# ir-control.net
KiCad netlist of a schematic drawn in EAGLE
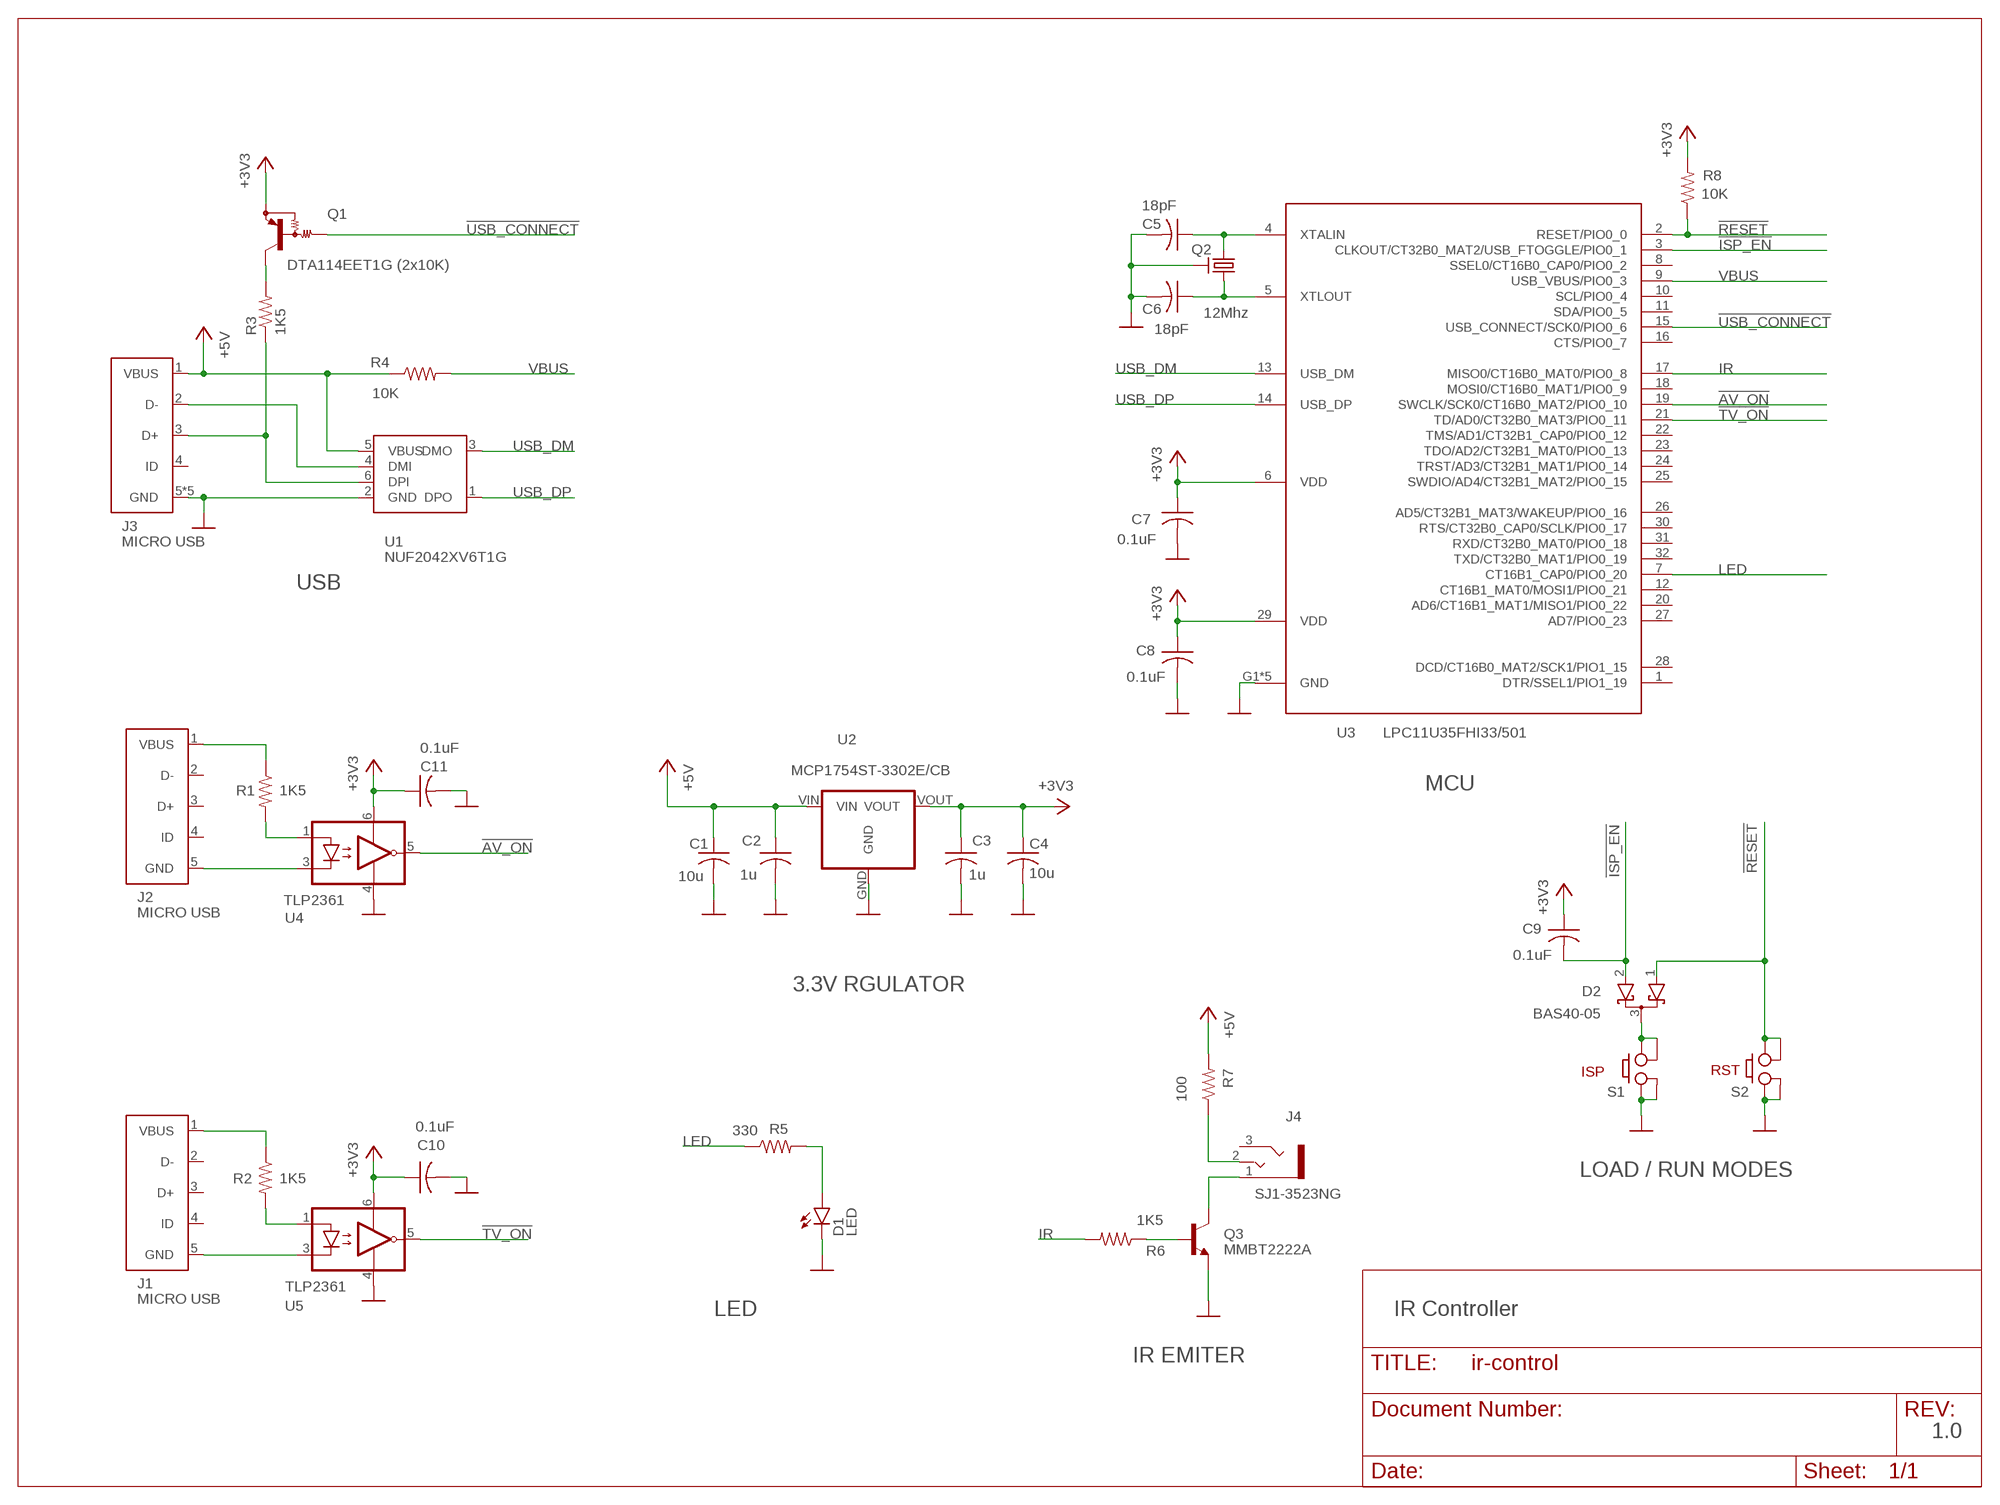
[diagram p0: schematic, sheet 1]

(export (version "E")
  (design (tool "Eeschema 10.0.6"))
  (components
    (comp (ref "C1")
      (value "10u")
      (footprint "eagle-import:C0805K")
      (libsource (lib "eagle-import") (part "CC0805K"))
    )
    (comp (ref "C2")
      (value "1u")
      (footprint "eagle-import:C0603K")
      (libsource (lib "eagle-import") (part "CC0603K"))
    )
    (comp (ref "C3")
      (value "1u")
      (footprint "eagle-import:C0603K")
      (libsource (lib "eagle-import") (part "CC0603K"))
    )
    (comp (ref "C4")
      (value "10u")
      (footprint "eagle-import:C0805K")
      (libsource (lib "eagle-import") (part "CC0805K"))
    )
    (comp (ref "C5")
      (value "18pF")
      (footprint "eagle-import:C0402K")
      (libsource (lib "eagle-import") (part "CC0402K"))
    )
    (comp (ref "C6")
      (value "18pF")
      (footprint "eagle-import:C0402K")
      (libsource (lib "eagle-import") (part "CC0402K"))
    )
    (comp (ref "C7")
      (value "0.1uF")
      (footprint "eagle-import:C0402K")
      (libsource (lib "eagle-import") (part "CC0402K"))
    )
    (comp (ref "C8")
      (value "0.1uF")
      (footprint "eagle-import:C0402K")
      (libsource (lib "eagle-import") (part "CC0402K"))
    )
    (comp (ref "C9")
      (value "0.1uF")
      (footprint "eagle-import:C0402K")
      (libsource (lib "eagle-import") (part "CC0402K"))
    )
    (comp (ref "C10")
      (value "0.1uF")
      (footprint "eagle-import:C0402K")
      (libsource (lib "eagle-import") (part "CC0402K"))
    )
    (comp (ref "C11")
      (value "0.1uF")
      (footprint "eagle-import:C0402K")
      (libsource (lib "eagle-import") (part "CC0402K"))
    )
    (comp (ref "D1")
      (value "LED")
      (footprint "eagle-import:LED")
      (libsource (lib "eagle-import") (part "LED"))
    )
    (comp (ref "D2")
      (value "BAS40-05")
      (footprint "eagle-import:SOT23")
      (libsource (lib "eagle-import") (part "BAS40-05"))
    )
    (comp (ref "J1")
      (value "MICRO USB")
      (footprint "eagle-import:USB-MICRO")
      (libsource (lib "eagle-import") (part "USB-CONN-UNSHIELDED"))
    )
    (comp (ref "J2")
      (value "MICRO USB")
      (footprint "eagle-import:USB-MICRO")
      (libsource (lib "eagle-import") (part "USB-CONN-UNSHIELDED"))
    )
    (comp (ref "J3")
      (value "MICRO USB")
      (footprint "eagle-import:USB-MICRO")
      (libsource (lib "eagle-import") (part "USB-CONN"))
    )
    (comp (ref "J4")
      (value "SJ1-3523NG")
      (footprint "eagle-import:JACK")
      (fields (field (name "MPN") "KLBR 1"))
      (libsource (lib "eagle-import") (part "JACKX"))
    )
    (comp (ref "Q1")
      (value "DTA114EET1G (2x10K)")
      (footprint "eagle-import:SC75-BEC")
      (libsource (lib "eagle-import") (part "PNP-BIASED"))
    )
    (comp (ref "Q2")
      (value "12Mhz")
      (footprint "eagle-import:CRYSTAL")
      (libsource (lib "eagle-import") (part "CRYSTALCTS406"))
    )
    (comp (ref "Q3")
      (value "MMBT2222A")
      (footprint "eagle-import:SOT23")
      (libsource (lib "eagle-import") (part "NPN"))
    )
    (comp (ref "R1")
      (value "1K5")
      (footprint "eagle-import:R0402")
      (libsource (lib "eagle-import") (part "RR0402"))
    )
    (comp (ref "R2")
      (value "1K5")
      (footprint "eagle-import:R0402")
      (libsource (lib "eagle-import") (part "RR0402"))
    )
    (comp (ref "R3")
      (value "1K5")
      (footprint "eagle-import:R0402")
      (libsource (lib "eagle-import") (part "RR0402"))
    )
    (comp (ref "R4")
      (value "10K")
      (footprint "eagle-import:R0402")
      (libsource (lib "eagle-import") (part "RR0402"))
    )
    (comp (ref "R5")
      (value "330")
      (footprint "eagle-import:R0402")
      (libsource (lib "eagle-import") (part "RR0402"))
    )
    (comp (ref "R6")
      (value "1K5")
      (footprint "eagle-import:R0402")
      (libsource (lib "eagle-import") (part "RR0402"))
    )
    (comp (ref "R7")
      (value "100")
      (footprint "eagle-import:R0402")
      (libsource (lib "eagle-import") (part "RR0402"))
    )
    (comp (ref "R8")
      (value "10K")
      (footprint "eagle-import:R0402")
      (libsource (lib "eagle-import") (part "RR0402"))
    )
    (comp (ref "S1")
      (value "CKN10502CT-ND")
      (footprint "eagle-import:PUSH_BUTTON")
      (libsource (lib "eagle-import") (part "PUSH-BUTTON"))
    )
    (comp (ref "S2")
      (value "PUSH-BUTTON")
      (footprint "eagle-import:PUSH_BUTTON")
      (libsource (lib "eagle-import") (part "PUSH-BUTTON"))
    )
    (comp (ref "U1")
      (value "NUF2042XV6T1G")
      (footprint "eagle-import:SOT-563")
      (libsource (lib "eagle-import") (part "USB-ESD"))
    )
    (comp (ref "U2")
      (value "MCP1754ST-3302E/CB")
      (footprint "eagle-import:SOT-23A")
      (libsource (lib "eagle-import") (part "LDO"))
    )
    (comp (ref "U3")
      (value "LPC11U35FHI33/501")
      (footprint "eagle-import:HVQFN33-5MM")
      (libsource (lib "eagle-import") (part "LPC11U35FHN33/501"))
    )
    (comp (ref "U4")
      (value "TLP2361")
      (footprint "eagle-import:SO6")
      (libsource (lib "eagle-import") (part "OPTO_COUPLER"))
    )
    (comp (ref "U5")
      (value "TLP2361")
      (footprint "eagle-import:SO6")
      (libsource (lib "eagle-import") (part "OPTO_COUPLER"))
    )
  )
  (nets
    (net (code "1") (name "+3V3") (class "Default")
      (node (ref "C10") (pin "1") (pinfunction "1_1") (pintype "passive"))
      (node (ref "C11") (pin "1") (pinfunction "1_1") (pintype "passive"))
      (node (ref "C3") (pin "1") (pinfunction "1_1") (pintype "passive"))
      (node (ref "C4") (pin "1") (pinfunction "1_1") (pintype "passive"))
      (node (ref "C7") (pin "1") (pinfunction "1_1") (pintype "passive"))
      (node (ref "C8") (pin "1") (pinfunction "1_1") (pintype "passive"))
      (node (ref "C9") (pin "1") (pinfunction "1_1") (pintype "passive"))
      (node (ref "Q1") (pin "E") (pinfunction "E_E") (pintype "passive"))
      (node (ref "R8") (pin "2") (pinfunction "2_2") (pintype "passive"))
      (node (ref "U2") (pin "VOUT") (pinfunction "VOUT_VOUT") (pintype "power_in"))
      (node (ref "U3") (pin "29") (pinfunction "VDD_29") (pintype "bidirectional"))
      (node (ref "U3") (pin "6") (pinfunction "VDD_6") (pintype "bidirectional"))
      (node (ref "U4") (pin "6") (pinfunction "VCC_6") (pintype "passive"))
      (node (ref "U5") (pin "6") (pinfunction "VCC_6") (pintype "passive"))
    )
    (net (code "2") (name "+5V") (class "Default")
      (node (ref "C1") (pin "1") (pinfunction "1_1") (pintype "passive"))
      (node (ref "C2") (pin "1") (pinfunction "1_1") (pintype "passive"))
      (node (ref "J3") (pin "1") (pinfunction "VBUS_1") (pintype "bidirectional"))
      (node (ref "R4") (pin "1") (pinfunction "1_1") (pintype "passive"))
      (node (ref "R7") (pin "2") (pinfunction "2_2") (pintype "passive"))
      (node (ref "U1") (pin "5") (pinfunction "VBUS_5") (pintype "power_in"))
      (node (ref "U2") (pin "VIN") (pinfunction "VIN_VIN") (pintype "power_in"))
    )
    (net (code "3") (name "/IR") (class "Default")
      (node (ref "R6") (pin "2") (pinfunction "2_2") (pintype "passive"))
      (node (ref "U3") (pin "17") (pinfunction "MISO0/CT16B0_MAT0/PIO0_8_17") (pintype "bidirectional"))
    )
    (net (code "4") (name "/LED") (class "Default")
      (node (ref "R5") (pin "1") (pinfunction "1_1") (pintype "passive"))
      (node (ref "U3") (pin "7") (pinfunction "CT16B1_CAP0/PIO0_20_7") (pintype "bidirectional"))
    )
    (net (code "5") (name "/USB_DM") (class "Default")
      (node (ref "U1") (pin "3") (pinfunction "DMO_3") (pintype "passive"))
      (node (ref "U3") (pin "13") (pinfunction "USB_DM_13") (pintype "bidirectional"))
    )
    (net (code "6") (name "/USB_DP") (class "Default")
      (node (ref "U1") (pin "1") (pinfunction "DPO_1") (pintype "passive"))
      (node (ref "U3") (pin "14") (pinfunction "USB_DP_14") (pintype "bidirectional"))
    )
    (net (code "7") (name "/VBUS") (class "Default")
      (node (ref "R4") (pin "2") (pinfunction "2_2") (pintype "passive"))
      (node (ref "U3") (pin "9") (pinfunction "USB_VBUS/PIO0_3_9") (pintype "bidirectional"))
    )
    (net (code "8") (name "/~{AV_ON}") (class "Default")
      (node (ref "U3") (pin "19") (pinfunction "SWCLK/SCK0/CT16B0_MAT2/PIO0_10_19") (pintype "bidirectional"))
      (node (ref "U4") (pin "5") (pinfunction "OUT_5") (pintype "passive"))
    )
    (net (code "9") (name "/~{ISP_EN}") (class "Default")
      (node (ref "C9") (pin "2") (pinfunction "2_2") (pintype "passive"))
      (node (ref "D2") (pin "2") (pinfunction "A2_2") (pintype "passive"))
      (node (ref "U3") (pin "3") (pinfunction "CLKOUT/CT32B0_MAT2/USB_FTOGGLE/PIO0_1_3") (pintype "bidirectional"))
    )
    (net (code "10") (name "/~{RESET}") (class "Default")
      (node (ref "D2") (pin "1") (pinfunction "A1_1") (pintype "passive"))
      (node (ref "R8") (pin "1") (pinfunction "1_1") (pintype "passive"))
      (node (ref "S2") (pin "B1") (pinfunction "B1_B1") (pintype "passive"))
      (node (ref "S2") (pin "B1P") (pinfunction "B1_B1P") (pintype "passive"))
      (node (ref "S2") (pin "B2") (pinfunction "B2_B2") (pintype "passive"))
      (node (ref "S2") (pin "B2P") (pinfunction "B2_B2P") (pintype "passive"))
      (node (ref "U3") (pin "2") (pinfunction "RESET/PIO0_0_2") (pintype "bidirectional"))
    )
    (net (code "11") (name "/~{TV_ON}") (class "Default")
      (node (ref "U3") (pin "21") (pinfunction "TD/AD0/CT32B0_MAT3/PIO0_11_21") (pintype "bidirectional"))
      (node (ref "U5") (pin "5") (pinfunction "OUT_5") (pintype "passive"))
    )
    (net (code "12") (name "/~{USB_CONNECT}") (class "Default")
      (node (ref "Q1") (pin "B") (pinfunction "B_B") (pintype "passive"))
      (node (ref "U3") (pin "15") (pinfunction "USB_CONNECT/SCK0/PIO0_6_15") (pintype "bidirectional"))
    )
    (net (code "13") (name "GND") (class "Default")
      (node (ref "C1") (pin "2") (pinfunction "2_2") (pintype "passive"))
      (node (ref "C10") (pin "2") (pinfunction "2_2") (pintype "passive"))
      (node (ref "C11") (pin "2") (pinfunction "2_2") (pintype "passive"))
      (node (ref "C2") (pin "2") (pinfunction "2_2") (pintype "passive"))
      (node (ref "C3") (pin "2") (pinfunction "2_2") (pintype "passive"))
      (node (ref "C4") (pin "2") (pinfunction "2_2") (pintype "passive"))
      (node (ref "C5") (pin "2") (pinfunction "2_2") (pintype "passive"))
      (node (ref "C6") (pin "2") (pinfunction "2_2") (pintype "passive"))
      (node (ref "C7") (pin "2") (pinfunction "2_2") (pintype "passive"))
      (node (ref "C8") (pin "2") (pinfunction "2_2") (pintype "passive"))
      (node (ref "D1") (pin "K") (pinfunction "C_K") (pintype "passive"))
      (node (ref "J3") (pin "5") (pinfunction "GND_5") (pintype "bidirectional"))
      (node (ref "J3") (pin "G1") (pinfunction "GND_G1") (pintype "bidirectional"))
      (node (ref "J3") (pin "G2") (pinfunction "GND_G2") (pintype "bidirectional"))
      (node (ref "J3") (pin "G3") (pinfunction "GND_G3") (pintype "bidirectional"))
      (node (ref "J3") (pin "G4") (pinfunction "GND_G4") (pintype "bidirectional"))
      (node (ref "Q2") (pin "2") (pinfunction "GND_2") (pintype "power_in"))
      (node (ref "Q2") (pin "4") (pinfunction "GND_4") (pintype "power_in"))
      (node (ref "Q3") (pin "2") (pinfunction "E_2") (pintype "passive"))
      (node (ref "S1") (pin "A1") (pinfunction "A1_A1") (pintype "passive"))
      (node (ref "S1") (pin "A1P") (pinfunction "A1_A1P") (pintype "passive"))
      (node (ref "S1") (pin "A2") (pinfunction "A2_A2") (pintype "passive"))
      (node (ref "S1") (pin "A2P") (pinfunction "A2_A2P") (pintype "passive"))
      (node (ref "S2") (pin "A1") (pinfunction "A1_A1") (pintype "passive"))
      (node (ref "S2") (pin "A1P") (pinfunction "A1_A1P") (pintype "passive"))
      (node (ref "S2") (pin "A2") (pinfunction "A2_A2") (pintype "passive"))
      (node (ref "S2") (pin "A2P") (pinfunction "A2_A2P") (pintype "passive"))
      (node (ref "U1") (pin "2") (pinfunction "GND_2") (pintype "power_in"))
      (node (ref "U2") (pin "GND") (pinfunction "GND_GND") (pintype "power_in"))
      (node (ref "U3") (pin "G1") (pinfunction "GND_G1") (pintype "bidirectional"))
      (node (ref "U3") (pin "G2") (pinfunction "GND_G2") (pintype "bidirectional"))
      (node (ref "U3") (pin "G3") (pinfunction "GND_G3") (pintype "bidirectional"))
      (node (ref "U3") (pin "G4") (pinfunction "GND_G4") (pintype "bidirectional"))
      (node (ref "U3") (pin "TAB") (pinfunction "GND_TAB") (pintype "bidirectional"))
      (node (ref "U4") (pin "4") (pinfunction "GND_4") (pintype "passive"))
      (node (ref "U5") (pin "4") (pinfunction "GND_4") (pintype "passive"))
    )
    (net (code "14") (name "Net-(D1-PadA)") (class "Default")
      (node (ref "D1") (pin "A") (pinfunction "A_A") (pintype "passive"))
      (node (ref "R5") (pin "2") (pinfunction "2_2") (pintype "passive"))
    )
    (net (code "15") (name "Net-(D2-C)") (class "Default")
      (node (ref "D2") (pin "3") (pinfunction "C_3") (pintype "passive"))
      (node (ref "S1") (pin "B1") (pinfunction "B1_B1") (pintype "passive"))
      (node (ref "S1") (pin "B1P") (pinfunction "B1_B1P") (pintype "passive"))
      (node (ref "S1") (pin "B2") (pinfunction "B2_B2") (pintype "passive"))
      (node (ref "S1") (pin "B2P") (pinfunction "B2_B2P") (pintype "passive"))
    )
    (net (code "16") (name "Net-(J1-GND)") (class "Default")
      (node (ref "J1") (pin "5") (pinfunction "GND_5") (pintype "bidirectional"))
      (node (ref "U5") (pin "3") (pinfunction "C_3") (pintype "passive"))
    )
    (net (code "17") (name "Net-(J1-VBUS)") (class "Default")
      (node (ref "J1") (pin "1") (pinfunction "VBUS_1") (pintype "bidirectional"))
      (node (ref "R2") (pin "1") (pinfunction "1_1") (pintype "passive"))
    )
    (net (code "18") (name "Net-(J2-GND)") (class "Default")
      (node (ref "J2") (pin "5") (pinfunction "GND_5") (pintype "bidirectional"))
      (node (ref "U4") (pin "3") (pinfunction "C_3") (pintype "passive"))
    )
    (net (code "19") (name "Net-(J2-VBUS)") (class "Default")
      (node (ref "J2") (pin "1") (pinfunction "VBUS_1") (pintype "bidirectional"))
      (node (ref "R1") (pin "1") (pinfunction "1_1") (pintype "passive"))
    )
    (net (code "20") (name "Net-(J3-D+)") (class "Default")
      (node (ref "J3") (pin "3") (pinfunction "D+_3") (pintype "bidirectional"))
      (node (ref "R3") (pin "1") (pinfunction "1_1") (pintype "passive"))
      (node (ref "U1") (pin "6") (pinfunction "DPI_6") (pintype "passive"))
    )
    (net (code "21") (name "Net-(J3-D-)") (class "Default")
      (node (ref "J3") (pin "2") (pinfunction "D-_2") (pintype "bidirectional"))
      (node (ref "U1") (pin "4") (pinfunction "DMI_4") (pintype "passive"))
    )
    (net (code "22") (name "Net-(J4-Pad2)") (class "Default")
      (node (ref "J4") (pin "2") (pinfunction "2_2") (pintype "passive"))
      (node (ref "R7") (pin "1") (pinfunction "1_1") (pintype "passive"))
    )
    (net (code "23") (name "Net-(Q1-PadC)") (class "Default")
      (node (ref "Q1") (pin "C") (pinfunction "C_C") (pintype "passive"))
      (node (ref "R3") (pin "2") (pinfunction "2_2") (pintype "passive"))
    )
    (net (code "24") (name "Net-(Q2-2)") (class "Default")
      (node (ref "C5") (pin "1") (pinfunction "1_1") (pintype "passive"))
      (node (ref "Q2") (pin "3") (pinfunction "2_3") (pintype "passive"))
      (node (ref "U3") (pin "4") (pinfunction "XTALIN_4") (pintype "bidirectional"))
    )
    (net (code "25") (name "Net-(Q3-B)") (class "Default")
      (node (ref "Q3") (pin "1") (pinfunction "B_1") (pintype "passive"))
      (node (ref "R6") (pin "1") (pinfunction "1_1") (pintype "passive"))
    )
    (net (code "26") (name "Net-(Q3-C)") (class "Default")
      (node (ref "J4") (pin "1") (pinfunction "1_1") (pintype "passive"))
      (node (ref "Q3") (pin "3") (pinfunction "C_3") (pintype "passive"))
    )
    (net (code "27") (name "Net-(U3-XTLOUT)") (class "Default")
      (node (ref "C6") (pin "1") (pinfunction "1_1") (pintype "passive"))
      (node (ref "Q2") (pin "1") (pinfunction "1_1") (pintype "passive"))
      (node (ref "U3") (pin "5") (pinfunction "XTLOUT_5") (pintype "bidirectional"))
    )
    (net (code "28") (name "Net-(U4-A)") (class "Default")
      (node (ref "R1") (pin "2") (pinfunction "2_2") (pintype "passive"))
      (node (ref "U4") (pin "1") (pinfunction "A_1") (pintype "passive"))
    )
    (net (code "29") (name "Net-(U5-A)") (class "Default")
      (node (ref "R2") (pin "2") (pinfunction "2_2") (pintype "passive"))
      (node (ref "U5") (pin "1") (pinfunction "A_1") (pintype "passive"))
    )
    (net (code "30") (name "unconnected-(J1-D+-Pad3)") (class "Default")
      (node (ref "J1") (pin "3") (pinfunction "D+_3") (pintype "bidirectional"))
    )
    (net (code "31") (name "unconnected-(J1-D--Pad2)") (class "Default")
      (node (ref "J1") (pin "2") (pinfunction "D-_2") (pintype "bidirectional"))
    )
    (net (code "32") (name "unconnected-(J1-ID-Pad4)") (class "Default")
      (node (ref "J1") (pin "4") (pinfunction "ID_4") (pintype "bidirectional"))
    )
    (net (code "33") (name "unconnected-(J2-D+-Pad3)") (class "Default")
      (node (ref "J2") (pin "3") (pinfunction "D+_3") (pintype "bidirectional"))
    )
    (net (code "34") (name "unconnected-(J2-D--Pad2)") (class "Default")
      (node (ref "J2") (pin "2") (pinfunction "D-_2") (pintype "bidirectional"))
    )
    (net (code "35") (name "unconnected-(J2-ID-Pad4)") (class "Default")
      (node (ref "J2") (pin "4") (pinfunction "ID_4") (pintype "bidirectional"))
    )
    (net (code "36") (name "unconnected-(J3-ID-Pad4)") (class "Default")
      (node (ref "J3") (pin "4") (pinfunction "ID_4") (pintype "bidirectional"))
    )
    (net (code "37") (name "unconnected-(J4-Pad3)") (class "Default")
      (node (ref "J4") (pin "3") (pinfunction "3_3") (pintype "passive"))
    )
    (net (code "38") (name "unconnected-(U3-AD5{slash}CT32B1_MAT3{slash}WAKEUP{slash}PIO0_16-Pad26)") (class "Default")
      (node (ref "U3") (pin "26") (pinfunction "AD5/CT32B1_MAT3/WAKEUP/PIO0_16_26") (pintype "bidirectional"))
    )
    (net (code "39") (name "unconnected-(U3-AD6{slash}CT16B1_MAT1{slash}MISO1{slash}PIO0_22-Pad20)") (class "Default")
      (node (ref "U3") (pin "20") (pinfunction "AD6/CT16B1_MAT1/MISO1/PIO0_22_20") (pintype "bidirectional"))
    )
    (net (code "40") (name "unconnected-(U3-AD7{slash}PIO0_23-Pad27)") (class "Default")
      (node (ref "U3") (pin "27") (pinfunction "AD7/PIO0_23_27") (pintype "bidirectional"))
    )
    (net (code "41") (name "unconnected-(U3-CT16B1_MAT0{slash}MOSI1{slash}PIO0_21-Pad12)") (class "Default")
      (node (ref "U3") (pin "12") (pinfunction "CT16B1_MAT0/MOSI1/PIO0_21_12") (pintype "bidirectional"))
    )
    (net (code "42") (name "unconnected-(U3-CTS{slash}PIO0_7-Pad16)") (class "Default")
      (node (ref "U3") (pin "16") (pinfunction "CTS/PIO0_7_16") (pintype "bidirectional"))
    )
    (net (code "43") (name "unconnected-(U3-DCD{slash}CT16B0_MAT2{slash}SCK1{slash}PIO1_15-Pad28)") (class "Default")
      (node (ref "U3") (pin "28") (pinfunction "DCD/CT16B0_MAT2/SCK1/PIO1_15_28") (pintype "bidirectional"))
    )
    (net (code "44") (name "unconnected-(U3-DTR{slash}SSEL1{slash}PIO1_19-Pad1)") (class "Default")
      (node (ref "U3") (pin "1") (pinfunction "DTR/SSEL1/PIO1_19_1") (pintype "bidirectional"))
    )
    (net (code "45") (name "unconnected-(U3-MOSI0{slash}CT16B0_MAT1{slash}PIO0_9-Pad18)") (class "Default")
      (node (ref "U3") (pin "18") (pinfunction "MOSI0/CT16B0_MAT1/PIO0_9_18") (pintype "bidirectional"))
    )
    (net (code "46") (name "unconnected-(U3-RTS{slash}CT32B0_CAP0{slash}SCLK{slash}PIO0_17-Pad30)") (class "Default")
      (node (ref "U3") (pin "30") (pinfunction "RTS/CT32B0_CAP0/SCLK/PIO0_17_30") (pintype "bidirectional"))
    )
    (net (code "47") (name "unconnected-(U3-RXD{slash}CT32B0_MAT0{slash}PIO0_18-Pad31)") (class "Default")
      (node (ref "U3") (pin "31") (pinfunction "RXD/CT32B0_MAT0/PIO0_18_31") (pintype "bidirectional"))
    )
    (net (code "48") (name "unconnected-(U3-SCL{slash}PIO0_4-Pad10)") (class "Default")
      (node (ref "U3") (pin "10") (pinfunction "SCL/PIO0_4_10") (pintype "bidirectional"))
    )
    (net (code "49") (name "unconnected-(U3-SDA{slash}PIO0_5-Pad11)") (class "Default")
      (node (ref "U3") (pin "11") (pinfunction "SDA/PIO0_5_11") (pintype "bidirectional"))
    )
    (net (code "50") (name "unconnected-(U3-SSEL0{slash}CT16B0_CAP0{slash}PIO0_2-Pad8)") (class "Default")
      (node (ref "U3") (pin "8") (pinfunction "SSEL0/CT16B0_CAP0/PIO0_2_8") (pintype "bidirectional"))
    )
    (net (code "51") (name "unconnected-(U3-SWDIO{slash}AD4{slash}CT32B1_MAT2{slash}PIO0_15-Pad25)") (class "Default")
      (node (ref "U3") (pin "25") (pinfunction "SWDIO/AD4/CT32B1_MAT2/PIO0_15_25") (pintype "bidirectional"))
    )
    (net (code "52") (name "unconnected-(U3-TDO{slash}AD2{slash}CT32B1_MAT0{slash}PIO0_13-Pad23)") (class "Default")
      (node (ref "U3") (pin "23") (pinfunction "TDO/AD2/CT32B1_MAT0/PIO0_13_23") (pintype "bidirectional"))
    )
    (net (code "53") (name "unconnected-(U3-TMS{slash}AD1{slash}CT32B1_CAP0{slash}PIO0_12-Pad22)") (class "Default")
      (node (ref "U3") (pin "22") (pinfunction "TMS/AD1/CT32B1_CAP0/PIO0_12_22") (pintype "bidirectional"))
    )
    (net (code "54") (name "unconnected-(U3-TRST{slash}AD3{slash}CT32B1_MAT1{slash}PIO0_14-Pad24)") (class "Default")
      (node (ref "U3") (pin "24") (pinfunction "TRST/AD3/CT32B1_MAT1/PIO0_14_24") (pintype "bidirectional"))
    )
    (net (code "55") (name "unconnected-(U3-TXD{slash}CT32B0_MAT1{slash}PIO0_19-Pad32)") (class "Default")
      (node (ref "U3") (pin "32") (pinfunction "TXD/CT32B0_MAT1/PIO0_19_32") (pintype "bidirectional"))
    )
  )
)
